# Beambreak_Array_S_-_Emmiter.net
KiCad netlist of a schematic drawn in Altium Designer
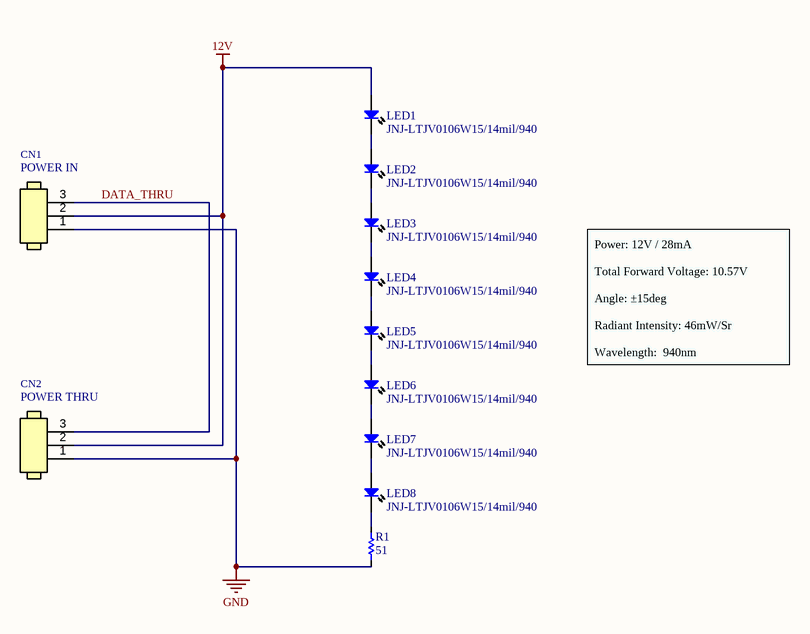
[diagram p0: Beambreak Array S - Emmiter.SchDoc]

(export (version "E")
  (design (tool "Eeschema 10.0.6"))
  (components
    (comp (ref "CN1")
      (value "POWER IN")
      (footprint "EH_1X3P")
      (description "Connector Header, EH Series, 3 Position, 2.5mm, Through Hole, Press-Fit, Solder, Natural")
      (fields (field (name "PARTNUMBER") "B3B-EH-A(LF)(SN)"))
      (libsource (lib "Sainsbury Wellcome Centre") (part "Wire to Board 1x3"))
    )
    (comp (ref "CN2")
      (value "POWER THRU")
      (footprint "EH_1X3P")
      (description "Connector Header, EH Series, 3 Position, 2.5mm, Through Hole, Press-Fit, Solder, Natural")
      (fields (field (name "PARTNUMBER") "B3B-EH-A(LF)(SN)"))
      (libsource (lib "Sainsbury Wellcome Centre") (part "Wire to Board 1x3"))
    )
    (comp (ref "LED1")
      (value "LED2835_IR_940nm")
      (footprint "LED_CHIP_3528 - lens - S")
      (description "240mW/sr 5V 100mA 1.4V~2.1V 925nm~955nm SMD2835-2P LED")
      (fields (field (name "PARTNUMBER") "JNJ-LTJV0106W15/14mil/940"))
      (libsource (lib "Sainsbury Wellcome Centre") (part "LED-IR"))
    )
    (comp (ref "LED2")
      (value "LED2835_IR_940nm")
      (footprint "LED_CHIP_3528 - lens - S")
      (description "240mW/sr 5V 100mA 1.4V~2.1V 925nm~955nm SMD2835-2P LED")
      (fields (field (name "PARTNUMBER") "JNJ-LTJV0106W15/14mil/940"))
      (libsource (lib "Sainsbury Wellcome Centre") (part "LED-IR"))
    )
    (comp (ref "LED3")
      (value "LED2835_IR_940nm")
      (footprint "LED_CHIP_3528 - lens - S")
      (description "240mW/sr 5V 100mA 1.4V~2.1V 925nm~955nm SMD2835-2P LED")
      (fields (field (name "PARTNUMBER") "JNJ-LTJV0106W15/14mil/940"))
      (libsource (lib "Sainsbury Wellcome Centre") (part "LED-IR"))
    )
    (comp (ref "LED4")
      (value "LED2835_IR_940nm")
      (footprint "LED_CHIP_3528 - lens - S")
      (description "240mW/sr 5V 100mA 1.4V~2.1V 925nm~955nm SMD2835-2P LED")
      (fields (field (name "PARTNUMBER") "JNJ-LTJV0106W15/14mil/940"))
      (libsource (lib "Sainsbury Wellcome Centre") (part "LED-IR"))
    )
    (comp (ref "LED5")
      (value "LED2835_IR_940nm")
      (footprint "LED_CHIP_3528 - lens - S")
      (description "240mW/sr 5V 100mA 1.4V~2.1V 925nm~955nm SMD2835-2P LED")
      (fields (field (name "PARTNUMBER") "JNJ-LTJV0106W15/14mil/940"))
      (libsource (lib "Sainsbury Wellcome Centre") (part "LED-IR"))
    )
    (comp (ref "LED6")
      (value "LED2835_IR_940nm")
      (footprint "LED_CHIP_3528 - lens - S")
      (description "240mW/sr 5V 100mA 1.4V~2.1V 925nm~955nm SMD2835-2P LED")
      (fields (field (name "PARTNUMBER") "JNJ-LTJV0106W15/14mil/940"))
      (libsource (lib "Sainsbury Wellcome Centre") (part "LED-IR"))
    )
    (comp (ref "LED7")
      (value "LED2835_IR_940nm")
      (footprint "LED_CHIP_3528 - lens - S")
      (description "240mW/sr 5V 100mA 1.4V~2.1V 925nm~955nm SMD2835-2P LED")
      (fields (field (name "PARTNUMBER") "JNJ-LTJV0106W15/14mil/940"))
      (libsource (lib "Sainsbury Wellcome Centre") (part "LED-IR"))
    )
    (comp (ref "LED8")
      (value "LED2835_IR_940nm")
      (footprint "LED_CHIP_3528 - lens - S")
      (description "240mW/sr 5V 100mA 1.4V~2.1V 925nm~955nm SMD2835-2P LED")
      (fields (field (name "PARTNUMBER") "JNJ-LTJV0106W15/14mil/940"))
      (libsource (lib "Sainsbury Wellcome Centre") (part "LED-IR"))
    )
    (comp (ref "R1")
      (value "51")
      (footprint "RES_CHIP_0805")
      (description "125mW Thick Film Resistors 150V ±100ppm/℃ ±1% 0805 Chip Resistor")
      (fields (field (name "TOLERANCE") "1%") (field (name "PARTNUMBER") "0805W8F510JT5E"))
      (libsource (lib "Sainsbury Wellcome Centre") (part "Res"))
    )
  )
  (nets
    (net (code "1") (name "/DATA_THRU") (class "Default")
      (node (ref "CN1") (pin "3") (pinfunction "3_3") (pintype "passive"))
      (node (ref "CN2") (pin "3") (pinfunction "3_3") (pintype "passive"))
    )
    (net (code "2") (name "12V") (class "Default")
      (node (ref "CN1") (pin "2") (pinfunction "2_2") (pintype "passive"))
      (node (ref "CN2") (pin "2") (pinfunction "2_2") (pintype "passive"))
      (node (ref "LED1") (pin "2") (pinfunction "A_2") (pintype "passive"))
    )
    (net (code "3") (name "GND") (class "Default")
      (node (ref "CN1") (pin "1") (pinfunction "1_1") (pintype "passive"))
      (node (ref "CN2") (pin "1") (pinfunction "1_1") (pintype "passive"))
      (node (ref "R1") (pin "1") (pinfunction "1_1") (pintype "passive"))
    )
    (net (code "4") (name "Net-(LED1-C)") (class "Default")
      (node (ref "LED1") (pin "1") (pinfunction "C_1") (pintype "passive"))
      (node (ref "LED2") (pin "2") (pinfunction "A_2") (pintype "passive"))
    )
    (net (code "5") (name "Net-(LED2-C)") (class "Default")
      (node (ref "LED2") (pin "1") (pinfunction "C_1") (pintype "passive"))
      (node (ref "LED3") (pin "2") (pinfunction "A_2") (pintype "passive"))
    )
    (net (code "6") (name "Net-(LED3-C)") (class "Default")
      (node (ref "LED3") (pin "1") (pinfunction "C_1") (pintype "passive"))
      (node (ref "LED4") (pin "2") (pinfunction "A_2") (pintype "passive"))
    )
    (net (code "7") (name "Net-(LED4-C)") (class "Default")
      (node (ref "LED4") (pin "1") (pinfunction "C_1") (pintype "passive"))
      (node (ref "LED5") (pin "2") (pinfunction "A_2") (pintype "passive"))
    )
    (net (code "8") (name "Net-(LED5-C)") (class "Default")
      (node (ref "LED5") (pin "1") (pinfunction "C_1") (pintype "passive"))
      (node (ref "LED6") (pin "2") (pinfunction "A_2") (pintype "passive"))
    )
    (net (code "9") (name "Net-(LED6-C)") (class "Default")
      (node (ref "LED6") (pin "1") (pinfunction "C_1") (pintype "passive"))
      (node (ref "LED7") (pin "2") (pinfunction "A_2") (pintype "passive"))
    )
    (net (code "10") (name "Net-(LED7-C)") (class "Default")
      (node (ref "LED7") (pin "1") (pinfunction "C_1") (pintype "passive"))
      (node (ref "LED8") (pin "2") (pinfunction "A_2") (pintype "passive"))
    )
    (net (code "11") (name "Net-(LED8-C)") (class "Default")
      (node (ref "LED8") (pin "1") (pinfunction "C_1") (pintype "passive"))
      (node (ref "R1") (pin "2") (pinfunction "2_2") (pintype "passive"))
    )
  )
)
